# Sheet7.net
KiCad netlist of a schematic drawn in Altium Designer
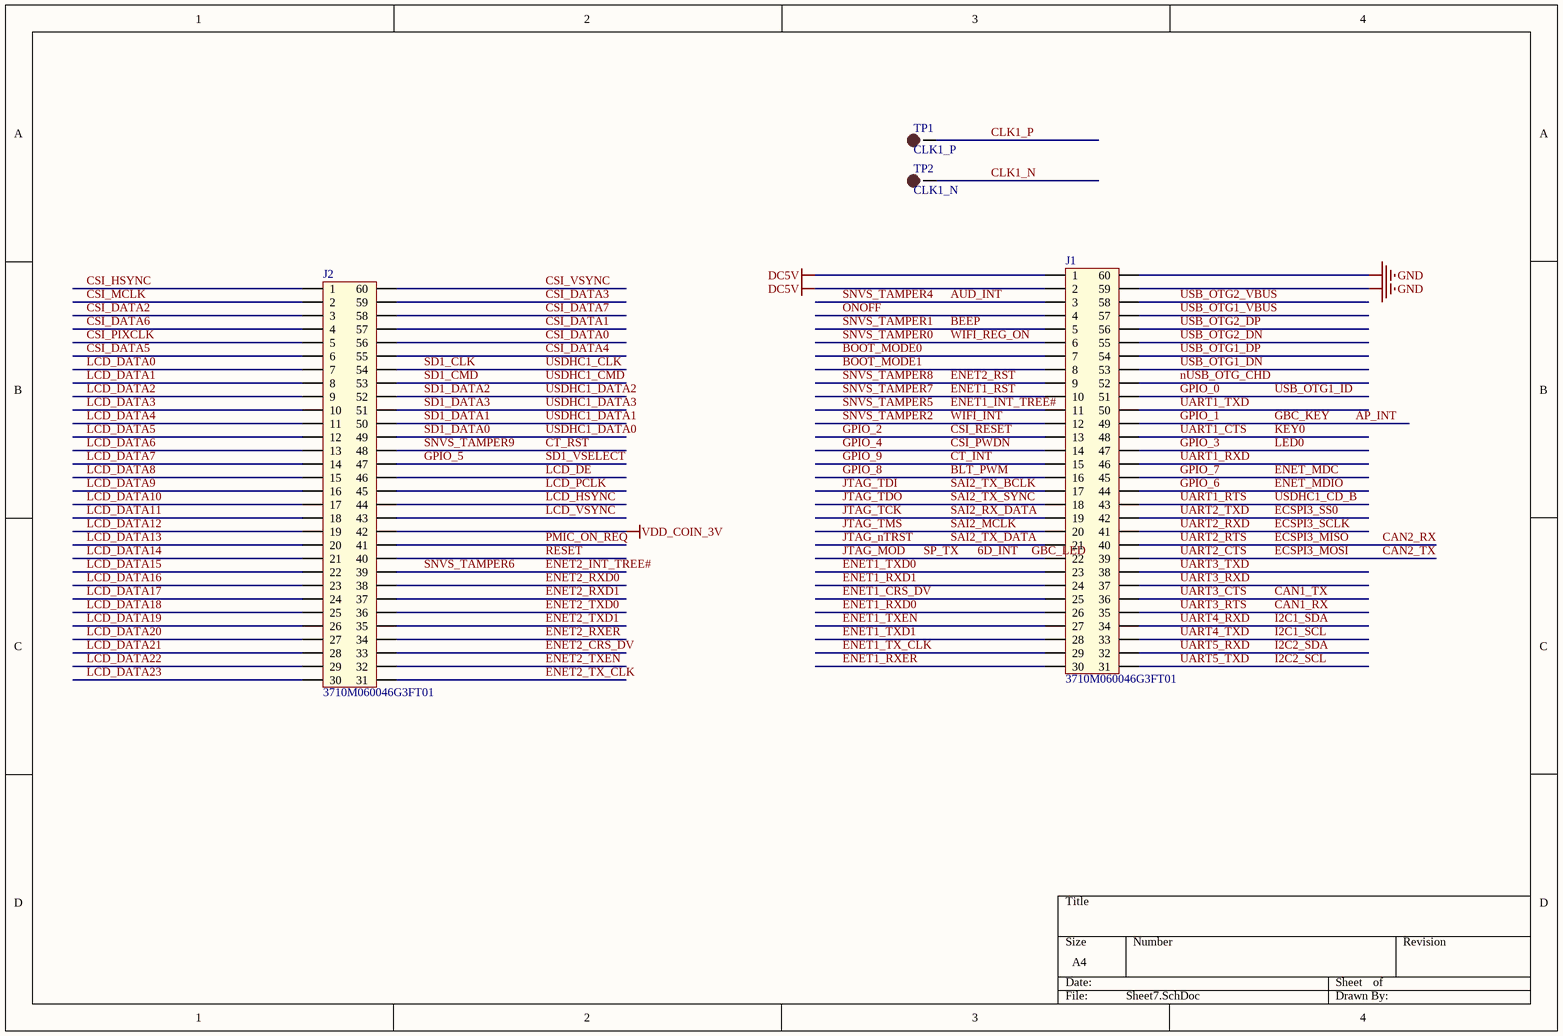
[diagram p0: Sheet7.SchDoc]

(export (version "E")
  (design (tool "Eeschema 10.0.6"))
  (components
    (comp (ref "J1")
      (value "3710M060046G3FT01")
      (footprint "3710F060046G3FT01")
      (description "3710F060046G3FT01")
      (libsource (lib "IMX6ULL_CORE(核心板)_V1.4") (part "3710F"))
    )
    (comp (ref "J2")
      (value "3710M060046G3FT01")
      (footprint "3710F060046G3FT01")
      (description "3710F060046G3FT01")
      (libsource (lib "IMX6ULL_CORE(核心板)_V1.4") (part "3710F"))
    )
    (comp (ref "TP1")
      (value "CLK1_P")
      (footprint "TP-1.0")
      (description "测试点")
      (libsource (lib "IMX6ULL_CORE(核心板)_V1.4") (part "TEST-POINT"))
    )
    (comp (ref "TP2")
      (value "CLK1_N")
      (footprint "TP-1.0")
      (description "测试点")
      (libsource (lib "IMX6ULL_CORE(核心板)_V1.4") (part "TEST-POINT"))
    )
  )
  (nets
    (net (code "1") (name "/6D_INT") (class "Default")
      (node (ref "J1") (pin "22") (pinfunction "22_22") (pintype "passive"))
    )
    (net (code "2") (name "/AP_INT") (class "Default")
      (node (ref "J1") (pin "49") (pinfunction "49_49") (pintype "passive"))
    )
    (net (code "3") (name "/AUD_INT") (class "Default")
      (node (ref "J1") (pin "3") (pinfunction "3_3") (pintype "passive"))
    )
    (net (code "4") (name "/BEEP") (class "Default")
      (node (ref "J1") (pin "5") (pinfunction "5_5") (pintype "passive"))
    )
    (net (code "5") (name "/BLT_PWM") (class "Default")
      (node (ref "J1") (pin "16") (pinfunction "16_16") (pintype "passive"))
    )
    (net (code "6") (name "/BOOT_MODE0") (class "Default")
      (node (ref "J1") (pin "7") (pinfunction "7_7") (pintype "passive"))
    )
    (net (code "7") (name "/BOOT_MODE1") (class "Default")
      (node (ref "J1") (pin "8") (pinfunction "8_8") (pintype "passive"))
    )
    (net (code "8") (name "/CAN1_RX") (class "Default")
      (node (ref "J1") (pin "35") (pinfunction "35_35") (pintype "passive"))
    )
    (net (code "9") (name "/CAN1_TX") (class "Default")
      (node (ref "J1") (pin "36") (pinfunction "36_36") (pintype "passive"))
    )
    (net (code "10") (name "/CAN2_RX") (class "Default")
      (node (ref "J1") (pin "40") (pinfunction "40_40") (pintype "passive"))
    )
    (net (code "11") (name "/CAN2_TX") (class "Default")
      (node (ref "J1") (pin "39") (pinfunction "39_39") (pintype "passive"))
    )
    (net (code "12") (name "/CLK1_N") (class "Default")
      (node (ref "TP2") (pin "1") (pinfunction "1_1") (pintype "passive"))
    )
    (net (code "13") (name "/CLK1_P") (class "Default")
      (node (ref "TP1") (pin "1") (pinfunction "1_1") (pintype "passive"))
    )
    (net (code "14") (name "/CSI_DATA0") (class "Default")
      (node (ref "J2") (pin "56") (pinfunction "56_56") (pintype "passive"))
    )
    (net (code "15") (name "/CSI_DATA1") (class "Default")
      (node (ref "J2") (pin "57") (pinfunction "57_57") (pintype "passive"))
    )
    (net (code "16") (name "/CSI_DATA2") (class "Default")
      (node (ref "J2") (pin "3") (pinfunction "3_3") (pintype "passive"))
    )
    (net (code "17") (name "/CSI_DATA3") (class "Default")
      (node (ref "J2") (pin "59") (pinfunction "59_59") (pintype "passive"))
    )
    (net (code "18") (name "/CSI_DATA4") (class "Default")
      (node (ref "J2") (pin "55") (pinfunction "55_55") (pintype "passive"))
    )
    (net (code "19") (name "/CSI_DATA5") (class "Default")
      (node (ref "J2") (pin "6") (pinfunction "6_6") (pintype "passive"))
    )
    (net (code "20") (name "/CSI_DATA6") (class "Default")
      (node (ref "J2") (pin "4") (pinfunction "4_4") (pintype "passive"))
    )
    (net (code "21") (name "/CSI_DATA7") (class "Default")
      (node (ref "J2") (pin "58") (pinfunction "58_58") (pintype "passive"))
    )
    (net (code "22") (name "/CSI_HSYNC") (class "Default")
      (node (ref "J2") (pin "1") (pinfunction "1_1") (pintype "passive"))
    )
    (net (code "23") (name "/CSI_MCLK") (class "Default")
      (node (ref "J2") (pin "2") (pinfunction "2_2") (pintype "passive"))
    )
    (net (code "24") (name "/CSI_PIXCLK") (class "Default")
      (node (ref "J2") (pin "5") (pinfunction "5_5") (pintype "passive"))
    )
    (net (code "25") (name "/CSI_PWDN") (class "Default")
      (node (ref "J1") (pin "14") (pinfunction "14_14") (pintype "passive"))
    )
    (net (code "26") (name "/CSI_RESET") (class "Default")
      (node (ref "J1") (pin "13") (pinfunction "13_13") (pintype "passive"))
    )
    (net (code "27") (name "/CSI_VSYNC") (class "Default")
      (node (ref "J2") (pin "60") (pinfunction "60_60") (pintype "passive"))
    )
    (net (code "28") (name "/CT_INT") (class "Default")
      (node (ref "J1") (pin "15") (pinfunction "15_15") (pintype "passive"))
    )
    (net (code "29") (name "/CT_RST") (class "Default")
      (node (ref "J2") (pin "48") (pinfunction "48_48") (pintype "passive"))
    )
    (net (code "30") (name "/ECSPI3_SCLK") (class "Default")
      (node (ref "J1") (pin "41") (pinfunction "41_41") (pintype "passive"))
    )
    (net (code "31") (name "/ECSPI3_SS0") (class "Default")
      (node (ref "J1") (pin "42") (pinfunction "42_42") (pintype "passive"))
    )
    (net (code "32") (name "/ENET1_CRS_DV") (class "Default")
      (node (ref "J1") (pin "25") (pinfunction "25_25") (pintype "passive"))
    )
    (net (code "33") (name "/ENET1_INT_TREE#") (class "Default")
      (node (ref "J1") (pin "11") (pinfunction "11_11") (pintype "passive"))
    )
    (net (code "34") (name "/ENET1_RST") (class "Default")
      (node (ref "J1") (pin "10") (pinfunction "10_10") (pintype "passive"))
    )
    (net (code "35") (name "/ENET1_RXD0") (class "Default")
      (node (ref "J1") (pin "26") (pinfunction "26_26") (pintype "passive"))
    )
    (net (code "36") (name "/ENET1_RXD1") (class "Default")
      (node (ref "J1") (pin "24") (pinfunction "24_24") (pintype "passive"))
    )
    (net (code "37") (name "/ENET1_RXER") (class "Default")
      (node (ref "J1") (pin "30") (pinfunction "30_30") (pintype "passive"))
    )
    (net (code "38") (name "/ENET1_TXD0") (class "Default")
      (node (ref "J1") (pin "23") (pinfunction "23_23") (pintype "passive"))
    )
    (net (code "39") (name "/ENET1_TXD1") (class "Default")
      (node (ref "J1") (pin "28") (pinfunction "28_28") (pintype "passive"))
    )
    (net (code "40") (name "/ENET1_TXEN") (class "Default")
      (node (ref "J1") (pin "27") (pinfunction "27_27") (pintype "passive"))
    )
    (net (code "41") (name "/ENET1_TX_CLK") (class "Default")
      (node (ref "J1") (pin "29") (pinfunction "29_29") (pintype "passive"))
    )
    (net (code "42") (name "/ENET2_CRS_DV") (class "Default")
      (node (ref "J2") (pin "33") (pinfunction "33_33") (pintype "passive"))
    )
    (net (code "43") (name "/ENET2_INT_TREE#") (class "Default")
      (node (ref "J2") (pin "39") (pinfunction "39_39") (pintype "passive"))
    )
    (net (code "44") (name "/ENET2_RST") (class "Default")
      (node (ref "J1") (pin "9") (pinfunction "9_9") (pintype "passive"))
    )
    (net (code "45") (name "/ENET2_RXD0") (class "Default")
      (node (ref "J2") (pin "38") (pinfunction "38_38") (pintype "passive"))
    )
    (net (code "46") (name "/ENET2_RXD1") (class "Default")
      (node (ref "J2") (pin "37") (pinfunction "37_37") (pintype "passive"))
    )
    (net (code "47") (name "/ENET2_RXER") (class "Default")
      (node (ref "J2") (pin "34") (pinfunction "34_34") (pintype "passive"))
    )
    (net (code "48") (name "/ENET2_TXD0") (class "Default")
      (node (ref "J2") (pin "36") (pinfunction "36_36") (pintype "passive"))
    )
    (net (code "49") (name "/ENET2_TXD1") (class "Default")
      (node (ref "J2") (pin "35") (pinfunction "35_35") (pintype "passive"))
    )
    (net (code "50") (name "/ENET2_TXEN") (class "Default")
      (node (ref "J2") (pin "32") (pinfunction "32_32") (pintype "passive"))
    )
    (net (code "51") (name "/ENET2_TX_CLK") (class "Default")
      (node (ref "J2") (pin "31") (pinfunction "31_31") (pintype "passive"))
    )
    (net (code "52") (name "/ENET_MDC") (class "Default")
      (node (ref "J1") (pin "45") (pinfunction "45_45") (pintype "passive"))
    )
    (net (code "53") (name "/ENET_MDIO") (class "Default")
      (node (ref "J1") (pin "44") (pinfunction "44_44") (pintype "passive"))
    )
    (net (code "54") (name "/GPIO_0") (class "Default")
      (node (ref "J1") (pin "51") (pinfunction "51_51") (pintype "passive"))
    )
    (net (code "55") (name "/GPIO_3") (class "Default")
      (node (ref "J1") (pin "47") (pinfunction "47_47") (pintype "passive"))
    )
    (net (code "56") (name "/GPIO_5") (class "Default")
      (node (ref "J2") (pin "47") (pinfunction "47_47") (pintype "passive"))
    )
    (net (code "57") (name "/I2C1_SCL") (class "Default")
      (node (ref "J1") (pin "33") (pinfunction "33_33") (pintype "passive"))
    )
    (net (code "58") (name "/I2C1_SDA") (class "Default")
      (node (ref "J1") (pin "34") (pinfunction "34_34") (pintype "passive"))
    )
    (net (code "59") (name "/I2C2_SCL") (class "Default")
      (node (ref "J1") (pin "31") (pinfunction "31_31") (pintype "passive"))
    )
    (net (code "60") (name "/I2C2_SDA") (class "Default")
      (node (ref "J1") (pin "32") (pinfunction "32_32") (pintype "passive"))
    )
    (net (code "61") (name "/JTAG_TCK") (class "Default")
      (node (ref "J1") (pin "19") (pinfunction "19_19") (pintype "passive"))
    )
    (net (code "62") (name "/JTAG_TDI") (class "Default")
      (node (ref "J1") (pin "17") (pinfunction "17_17") (pintype "passive"))
    )
    (net (code "63") (name "/JTAG_TDO") (class "Default")
      (node (ref "J1") (pin "18") (pinfunction "18_18") (pintype "passive"))
    )
    (net (code "64") (name "/JTAG_TMS") (class "Default")
      (node (ref "J1") (pin "20") (pinfunction "20_20") (pintype "passive"))
    )
    (net (code "65") (name "/JTAG_nTRST") (class "Default")
      (node (ref "J1") (pin "21") (pinfunction "21_21") (pintype "passive"))
    )
    (net (code "66") (name "/KEY0") (class "Default")
      (node (ref "J1") (pin "48") (pinfunction "48_48") (pintype "passive"))
    )
    (net (code "67") (name "/LCD_DATA0") (class "Default")
      (node (ref "J2") (pin "7") (pinfunction "7_7") (pintype "passive"))
    )
    (net (code "68") (name "/LCD_DATA1") (class "Default")
      (node (ref "J2") (pin "8") (pinfunction "8_8") (pintype "passive"))
    )
    (net (code "69") (name "/LCD_DATA2") (class "Default")
      (node (ref "J2") (pin "9") (pinfunction "9_9") (pintype "passive"))
    )
    (net (code "70") (name "/LCD_DATA3") (class "Default")
      (node (ref "J2") (pin "10") (pinfunction "10_10") (pintype "passive"))
    )
    (net (code "71") (name "/LCD_DATA4") (class "Default")
      (node (ref "J2") (pin "11") (pinfunction "11_11") (pintype "passive"))
    )
    (net (code "72") (name "/LCD_DATA5") (class "Default")
      (node (ref "J2") (pin "12") (pinfunction "12_12") (pintype "passive"))
    )
    (net (code "73") (name "/LCD_DATA6") (class "Default")
      (node (ref "J2") (pin "13") (pinfunction "13_13") (pintype "passive"))
    )
    (net (code "74") (name "/LCD_DATA7") (class "Default")
      (node (ref "J2") (pin "14") (pinfunction "14_14") (pintype "passive"))
    )
    (net (code "75") (name "/LCD_DATA8") (class "Default")
      (node (ref "J2") (pin "15") (pinfunction "15_15") (pintype "passive"))
    )
    (net (code "76") (name "/LCD_DATA9") (class "Default")
      (node (ref "J2") (pin "16") (pinfunction "16_16") (pintype "passive"))
    )
    (net (code "77") (name "/LCD_DATA10") (class "Default")
      (node (ref "J2") (pin "17") (pinfunction "17_17") (pintype "passive"))
    )
    (net (code "78") (name "/LCD_DATA11") (class "Default")
      (node (ref "J2") (pin "18") (pinfunction "18_18") (pintype "passive"))
    )
    (net (code "79") (name "/LCD_DATA12") (class "Default")
      (node (ref "J2") (pin "19") (pinfunction "19_19") (pintype "passive"))
    )
    (net (code "80") (name "/LCD_DATA13") (class "Default")
      (node (ref "J2") (pin "20") (pinfunction "20_20") (pintype "passive"))
    )
    (net (code "81") (name "/LCD_DATA14") (class "Default")
      (node (ref "J2") (pin "21") (pinfunction "21_21") (pintype "passive"))
    )
    (net (code "82") (name "/LCD_DATA15") (class "Default")
      (node (ref "J2") (pin "22") (pinfunction "22_22") (pintype "passive"))
    )
    (net (code "83") (name "/LCD_DATA16") (class "Default")
      (node (ref "J2") (pin "23") (pinfunction "23_23") (pintype "passive"))
    )
    (net (code "84") (name "/LCD_DATA17") (class "Default")
      (node (ref "J2") (pin "24") (pinfunction "24_24") (pintype "passive"))
    )
    (net (code "85") (name "/LCD_DATA18") (class "Default")
      (node (ref "J2") (pin "25") (pinfunction "25_25") (pintype "passive"))
    )
    (net (code "86") (name "/LCD_DATA19") (class "Default")
      (node (ref "J2") (pin "26") (pinfunction "26_26") (pintype "passive"))
    )
    (net (code "87") (name "/LCD_DATA20") (class "Default")
      (node (ref "J2") (pin "27") (pinfunction "27_27") (pintype "passive"))
    )
    (net (code "88") (name "/LCD_DATA21") (class "Default")
      (node (ref "J2") (pin "28") (pinfunction "28_28") (pintype "passive"))
    )
    (net (code "89") (name "/LCD_DATA22") (class "Default")
      (node (ref "J2") (pin "29") (pinfunction "29_29") (pintype "passive"))
    )
    (net (code "90") (name "/LCD_DATA23") (class "Default")
      (node (ref "J2") (pin "30") (pinfunction "30_30") (pintype "passive"))
    )
    (net (code "91") (name "/LCD_DE") (class "Default")
      (node (ref "J2") (pin "46") (pinfunction "46_46") (pintype "passive"))
    )
    (net (code "92") (name "/LCD_HSYNC") (class "Default")
      (node (ref "J2") (pin "44") (pinfunction "44_44") (pintype "passive"))
    )
    (net (code "93") (name "/LCD_PCLK") (class "Default")
      (node (ref "J2") (pin "45") (pinfunction "45_45") (pintype "passive"))
    )
    (net (code "94") (name "/LCD_VSYNC") (class "Default")
      (node (ref "J2") (pin "43") (pinfunction "43_43") (pintype "passive"))
    )
    (net (code "95") (name "/ONOFF") (class "Default")
      (node (ref "J1") (pin "4") (pinfunction "4_4") (pintype "passive"))
    )
    (net (code "96") (name "/PMIC_ON_REQ") (class "Default")
      (node (ref "J2") (pin "41") (pinfunction "41_41") (pintype "passive"))
    )
    (net (code "97") (name "/RESET") (class "Default")
      (node (ref "J2") (pin "40") (pinfunction "40_40") (pintype "passive"))
    )
    (net (code "98") (name "/SD1_CLK") (class "Default")
      (node (ref "J2") (pin "54") (pinfunction "54_54") (pintype "passive"))
    )
    (net (code "99") (name "/SD1_CMD") (class "Default")
      (node (ref "J2") (pin "53") (pinfunction "53_53") (pintype "passive"))
    )
    (net (code "100") (name "/SD1_DATA0") (class "Default")
      (node (ref "J2") (pin "49") (pinfunction "49_49") (pintype "passive"))
    )
    (net (code "101") (name "/SD1_DATA1") (class "Default")
      (node (ref "J2") (pin "50") (pinfunction "50_50") (pintype "passive"))
    )
    (net (code "102") (name "/SD1_DATA2") (class "Default")
      (node (ref "J2") (pin "52") (pinfunction "52_52") (pintype "passive"))
    )
    (net (code "103") (name "/SD1_DATA3") (class "Default")
      (node (ref "J2") (pin "51") (pinfunction "51_51") (pintype "passive"))
    )
    (net (code "104") (name "/SNVS_TAMPER0") (class "Default")
      (node (ref "J1") (pin "6") (pinfunction "6_6") (pintype "passive"))
    )
    (net (code "105") (name "/SNVS_TAMPER2") (class "Default")
      (node (ref "J1") (pin "12") (pinfunction "12_12") (pintype "passive"))
    )
    (net (code "106") (name "/UART1_RTS") (class "Default")
      (node (ref "J1") (pin "43") (pinfunction "43_43") (pintype "passive"))
    )
    (net (code "107") (name "/UART1_RXD") (class "Default")
      (node (ref "J1") (pin "46") (pinfunction "46_46") (pintype "passive"))
    )
    (net (code "108") (name "/UART1_TXD") (class "Default")
      (node (ref "J1") (pin "50") (pinfunction "50_50") (pintype "passive"))
    )
    (net (code "109") (name "/UART3_RXD") (class "Default")
      (node (ref "J1") (pin "37") (pinfunction "37_37") (pintype "passive"))
    )
    (net (code "110") (name "/UART3_TXD") (class "Default")
      (node (ref "J1") (pin "38") (pinfunction "38_38") (pintype "passive"))
    )
    (net (code "111") (name "/USB_OTG1_DN") (class "Default")
      (node (ref "J1") (pin "53") (pinfunction "53_53") (pintype "passive"))
    )
    (net (code "112") (name "/USB_OTG1_DP") (class "Default")
      (node (ref "J1") (pin "54") (pinfunction "54_54") (pintype "passive"))
    )
    (net (code "113") (name "/USB_OTG1_VBUS") (class "Default")
      (node (ref "J1") (pin "57") (pinfunction "57_57") (pintype "passive"))
    )
    (net (code "114") (name "/USB_OTG2_DN") (class "Default")
      (node (ref "J1") (pin "55") (pinfunction "55_55") (pintype "passive"))
    )
    (net (code "115") (name "/USB_OTG2_DP") (class "Default")
      (node (ref "J1") (pin "56") (pinfunction "56_56") (pintype "passive"))
    )
    (net (code "116") (name "/USB_OTG2_VBUS") (class "Default")
      (node (ref "J1") (pin "58") (pinfunction "58_58") (pintype "passive"))
    )
    (net (code "117") (name "/nUSB_OTG_CHD") (class "Default")
      (node (ref "J1") (pin "52") (pinfunction "52_52") (pintype "passive"))
    )
    (net (code "118") (name "DC5V") (class "Default")
      (node (ref "J1") (pin "1") (pinfunction "1_1") (pintype "passive"))
      (node (ref "J1") (pin "2") (pinfunction "2_2") (pintype "passive"))
    )
    (net (code "119") (name "GND") (class "Default")
      (node (ref "J1") (pin "59") (pinfunction "59_59") (pintype "passive"))
      (node (ref "J1") (pin "60") (pinfunction "60_60") (pintype "passive"))
    )
    (net (code "120") (name "VDD_COIN_3V") (class "Default")
      (node (ref "J2") (pin "42") (pinfunction "42_42") (pintype "passive"))
    )
  )
)
